# M930C.net
KiCad netlist of a schematic drawn in EAGLE
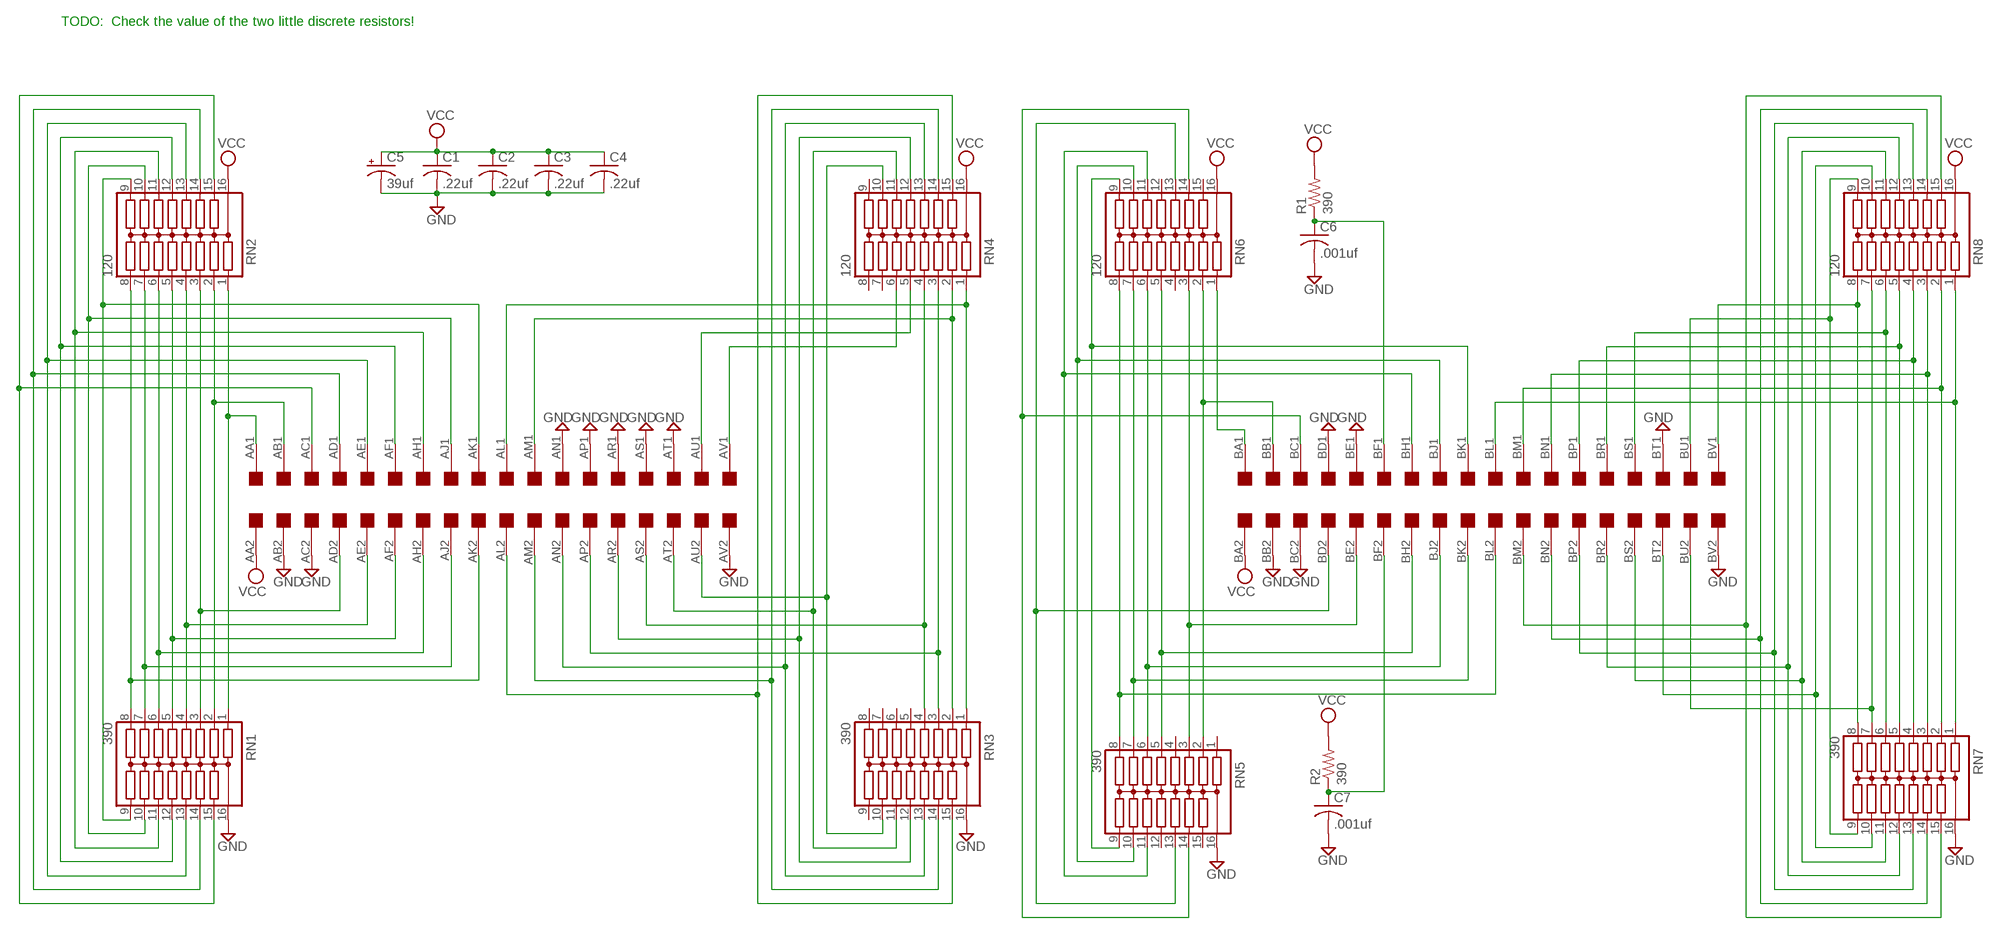
[diagram p0: schematic, sheet 1]

(export (version "E")
  (design (tool "Eeschema 10.0.6"))
  (components
    (comp (ref "C1")
      (value ".22uf")
      (footprint "eagle-import:C050-025X075")
      (libsource (lib "eagle-import") (part "C-US050-025X075"))
    )
    (comp (ref "C2")
      (value ".22uf")
      (footprint "eagle-import:C050-025X075")
      (libsource (lib "eagle-import") (part "C-US050-025X075"))
    )
    (comp (ref "C3")
      (value ".22uf")
      (footprint "eagle-import:C050-025X075")
      (libsource (lib "eagle-import") (part "C-US050-025X075"))
    )
    (comp (ref "C4")
      (value ".22uf")
      (footprint "eagle-import:C050-025X075")
      (libsource (lib "eagle-import") (part "C-US050-025X075"))
    )
    (comp (ref "C5")
      (value "39uf")
      (footprint "eagle-import:E15-5")
      (libsource (lib "eagle-import") (part "CPOL-USE15-5AXIAL"))
    )
    (comp (ref "C6")
      (value ".001uf")
      (footprint "eagle-import:C050-025X075")
      (libsource (lib "eagle-import") (part "C-US050-025X075"))
    )
    (comp (ref "C7")
      (value ".001uf")
      (footprint "eagle-import:C050-025X075")
      (libsource (lib "eagle-import") (part "C-US050-025X075"))
    )
    (comp (ref "R1")
      (value "390")
      (footprint "eagle-import:0207_10")
      (libsource (lib "eagle-import") (part "R-US_0207/10"))
    )
    (comp (ref "R2")
      (value "390")
      (footprint "eagle-import:0207_10")
      (libsource (lib "eagle-import") (part "R-US_0207/10"))
    )
    (comp (ref "RN1")
      (value "390")
      (footprint "eagle-import:DIL16")
      (libsource (lib "eagle-import") (part "15R"))
    )
    (comp (ref "RN2")
      (value "120")
      (footprint "eagle-import:DIL16")
      (libsource (lib "eagle-import") (part "15R"))
    )
    (comp (ref "RN3")
      (value "390")
      (footprint "eagle-import:DIL16")
      (libsource (lib "eagle-import") (part "15R"))
    )
    (comp (ref "RN4")
      (value "120")
      (footprint "eagle-import:DIL16")
      (libsource (lib "eagle-import") (part "15R"))
    )
    (comp (ref "RN5")
      (value "390")
      (footprint "eagle-import:DIL16")
      (libsource (lib "eagle-import") (part "15R"))
    )
    (comp (ref "RN6")
      (value "120")
      (footprint "eagle-import:DIL16")
      (libsource (lib "eagle-import") (part "15R"))
    )
    (comp (ref "RN7")
      (value "390")
      (footprint "eagle-import:DIL16")
      (libsource (lib "eagle-import") (part "15R"))
    )
    (comp (ref "RN8")
      (value "120")
      (footprint "eagle-import:DIL16")
      (libsource (lib "eagle-import") (part "15R"))
    )
    (comp (ref "U$1")
      (value "DOUBLE")
      (footprint "eagle-import:EDGE-CON4")
      (libsource (lib "eagle-import") (part "DOUBLE"))
    )
  )
  (nets
    (net (code "1") (name "GND") (class "Default")
      (node (ref "C1") (pin "2") (pinfunction "2_2") (pintype "passive"))
      (node (ref "C2") (pin "2") (pinfunction "2_2") (pintype "passive"))
      (node (ref "C3") (pin "2") (pinfunction "2_2") (pintype "passive"))
      (node (ref "C4") (pin "2") (pinfunction "2_2") (pintype "passive"))
      (node (ref "C5") (pin "-") (pinfunction "-_-") (pintype "passive"))
      (node (ref "C6") (pin "2") (pinfunction "2_2") (pintype "passive"))
      (node (ref "C7") (pin "2") (pinfunction "2_2") (pintype "passive"))
      (node (ref "RN1") (pin "16") (pinfunction "16_16") (pintype "passive"))
      (node (ref "RN3") (pin "16") (pinfunction "16_16") (pintype "passive"))
      (node (ref "RN5") (pin "16") (pinfunction "16_16") (pintype "passive"))
      (node (ref "RN7") (pin "16") (pinfunction "16_16") (pintype "passive"))
      (node (ref "U$1") (pin "AB2") (pinfunction "1_AB2") (pintype "bidirectional"))
      (node (ref "U$1") (pin "AC2") (pinfunction "1_AC2") (pintype "bidirectional"))
      (node (ref "U$1") (pin "AN1") (pinfunction "1_AN1") (pintype "bidirectional"))
      (node (ref "U$1") (pin "AP1") (pinfunction "1_AP1") (pintype "bidirectional"))
      (node (ref "U$1") (pin "AR1") (pinfunction "1_AR1") (pintype "bidirectional"))
      (node (ref "U$1") (pin "AS1") (pinfunction "1_AS1") (pintype "bidirectional"))
      (node (ref "U$1") (pin "AT1") (pinfunction "1_AT1") (pintype "bidirectional"))
      (node (ref "U$1") (pin "AV2") (pinfunction "1_AV2") (pintype "bidirectional"))
      (node (ref "U$1") (pin "BB2") (pinfunction "1_BB2") (pintype "bidirectional"))
      (node (ref "U$1") (pin "BC2") (pinfunction "1_BC2") (pintype "bidirectional"))
      (node (ref "U$1") (pin "BD1") (pinfunction "1_BD1") (pintype "bidirectional"))
      (node (ref "U$1") (pin "BE1") (pinfunction "1_BE1") (pintype "bidirectional"))
      (node (ref "U$1") (pin "BT1") (pinfunction "1_BT1") (pintype "bidirectional"))
      (node (ref "U$1") (pin "BV2") (pinfunction "1_BV2") (pintype "bidirectional"))
    )
    (net (code "2") (name "Net-(U$1A-1)") (class "Default")
      (node (ref "RN1") (pin "1") (pinfunction "1_1") (pintype "passive"))
      (node (ref "RN2") (pin "1") (pinfunction "1_1") (pintype "passive"))
      (node (ref "U$1") (pin "AA1") (pinfunction "1_AA1") (pintype "bidirectional"))
    )
    (net (code "3") (name "Net-(U$1AB-1)") (class "Default")
      (node (ref "RN3") (pin "12") (pinfunction "12_12") (pintype "passive"))
      (node (ref "RN4") (pin "12") (pinfunction "12_12") (pintype "passive"))
      (node (ref "U$1") (pin "AR2") (pinfunction "1_AR2") (pintype "bidirectional"))
    )
    (net (code "4") (name "Net-(U$1AD-1)") (class "Default")
      (node (ref "RN3") (pin "4") (pinfunction "4_4") (pintype "passive"))
      (node (ref "RN4") (pin "4") (pinfunction "4_4") (pintype "passive"))
      (node (ref "U$1") (pin "AS2") (pinfunction "1_AS2") (pintype "bidirectional"))
    )
    (net (code "5") (name "Net-(U$1AF-1)") (class "Default")
      (node (ref "RN3") (pin "11") (pinfunction "11_11") (pintype "passive"))
      (node (ref "RN4") (pin "11") (pinfunction "11_11") (pintype "passive"))
      (node (ref "U$1") (pin "AT2") (pinfunction "1_AT2") (pintype "bidirectional"))
    )
    (net (code "6") (name "Net-(U$1AG-1)") (class "Default")
      (node (ref "RN4") (pin "5") (pinfunction "5_5") (pintype "passive"))
      (node (ref "U$1") (pin "AU1") (pinfunction "1_AU1") (pintype "bidirectional"))
    )
    (net (code "7") (name "Net-(U$1AH-1)") (class "Default")
      (node (ref "RN3") (pin "10") (pinfunction "10_10") (pintype "passive"))
      (node (ref "RN4") (pin "10") (pinfunction "10_10") (pintype "passive"))
      (node (ref "U$1") (pin "AU2") (pinfunction "1_AU2") (pintype "bidirectional"))
    )
    (net (code "8") (name "Net-(U$1AI-1)") (class "Default")
      (node (ref "RN4") (pin "6") (pinfunction "6_6") (pintype "passive"))
      (node (ref "U$1") (pin "AV1") (pinfunction "1_AV1") (pintype "bidirectional"))
    )
    (net (code "9") (name "Net-(U$1AK-1)") (class "Default")
      (node (ref "RN6") (pin "1") (pinfunction "1_1") (pintype "passive"))
      (node (ref "U$1") (pin "BA1") (pinfunction "1_BA1") (pintype "bidirectional"))
    )
    (net (code "10") (name "Net-(U$1AM-1)") (class "Default")
      (node (ref "RN5") (pin "2") (pinfunction "2_2") (pintype "passive"))
      (node (ref "RN6") (pin "2") (pinfunction "2_2") (pintype "passive"))
      (node (ref "U$1") (pin "BB1") (pinfunction "1_BB1") (pintype "bidirectional"))
    )
    (net (code "11") (name "Net-(U$1AO-1)") (class "Default")
      (node (ref "RN5") (pin "14") (pinfunction "14_14") (pintype "passive"))
      (node (ref "RN6") (pin "14") (pinfunction "14_14") (pintype "passive"))
      (node (ref "U$1") (pin "BC1") (pinfunction "1_BC1") (pintype "bidirectional"))
    )
    (net (code "12") (name "Net-(U$1AR-1)") (class "Default")
      (node (ref "RN5") (pin "13") (pinfunction "13_13") (pintype "passive"))
      (node (ref "RN6") (pin "13") (pinfunction "13_13") (pintype "passive"))
      (node (ref "U$1") (pin "BD2") (pinfunction "1_BD2") (pintype "bidirectional"))
    )
    (net (code "13") (name "Net-(U$1AT-1)") (class "Default")
      (node (ref "RN5") (pin "3") (pinfunction "3_3") (pintype "passive"))
      (node (ref "RN6") (pin "3") (pinfunction "3_3") (pintype "passive"))
      (node (ref "U$1") (pin "BE2") (pinfunction "1_BE2") (pintype "bidirectional"))
    )
    (net (code "14") (name "Net-(U$1AU-1)") (class "Default")
      (node (ref "C6") (pin "1") (pinfunction "1_1") (pintype "passive"))
      (node (ref "R1") (pin "1") (pinfunction "1_1") (pintype "passive"))
      (node (ref "U$1") (pin "BF1") (pinfunction "1_BF1") (pintype "bidirectional"))
    )
    (net (code "15") (name "Net-(U$1AV-1)") (class "Default")
      (node (ref "C7") (pin "1") (pinfunction "1_1") (pintype "passive"))
      (node (ref "R2") (pin "1") (pinfunction "1_1") (pintype "passive"))
      (node (ref "U$1") (pin "BF2") (pinfunction "1_BF2") (pintype "bidirectional"))
    )
    (net (code "16") (name "Net-(U$1AW-1)") (class "Default")
      (node (ref "RN5") (pin "11") (pinfunction "11_11") (pintype "passive"))
      (node (ref "RN6") (pin "11") (pinfunction "11_11") (pintype "passive"))
      (node (ref "U$1") (pin "BH1") (pinfunction "1_BH1") (pintype "bidirectional"))
    )
    (net (code "17") (name "Net-(U$1AX-1)") (class "Default")
      (node (ref "RN5") (pin "5") (pinfunction "5_5") (pintype "passive"))
      (node (ref "RN6") (pin "5") (pinfunction "5_5") (pintype "passive"))
      (node (ref "U$1") (pin "BH2") (pinfunction "1_BH2") (pintype "bidirectional"))
    )
    (net (code "18") (name "Net-(U$1AY-1)") (class "Default")
      (node (ref "RN5") (pin "10") (pinfunction "10_10") (pintype "passive"))
      (node (ref "RN6") (pin "10") (pinfunction "10_10") (pintype "passive"))
      (node (ref "U$1") (pin "BJ1") (pinfunction "1_BJ1") (pintype "bidirectional"))
    )
    (net (code "19") (name "Net-(U$1AZ-1)") (class "Default")
      (node (ref "RN5") (pin "6") (pinfunction "6_6") (pintype "passive"))
      (node (ref "RN6") (pin "6") (pinfunction "6_6") (pintype "passive"))
      (node (ref "U$1") (pin "BJ2") (pinfunction "1_BJ2") (pintype "bidirectional"))
    )
    (net (code "20") (name "Net-(U$1BA-1)") (class "Default")
      (node (ref "RN5") (pin "9") (pinfunction "9_9") (pintype "passive"))
      (node (ref "RN6") (pin "9") (pinfunction "9_9") (pintype "passive"))
      (node (ref "U$1") (pin "BK1") (pinfunction "1_BK1") (pintype "bidirectional"))
    )
    (net (code "21") (name "Net-(U$1BB-1)") (class "Default")
      (node (ref "RN5") (pin "7") (pinfunction "7_7") (pintype "passive"))
      (node (ref "RN6") (pin "7") (pinfunction "7_7") (pintype "passive"))
      (node (ref "U$1") (pin "BK2") (pinfunction "1_BK2") (pintype "bidirectional"))
    )
    (net (code "22") (name "Net-(U$1BC-1)") (class "Default")
      (node (ref "RN7") (pin "1") (pinfunction "1_1") (pintype "passive"))
      (node (ref "RN8") (pin "1") (pinfunction "1_1") (pintype "passive"))
      (node (ref "U$1") (pin "BL1") (pinfunction "1_BL1") (pintype "bidirectional"))
    )
    (net (code "23") (name "Net-(U$1BD-1)") (class "Default")
      (node (ref "RN5") (pin "8") (pinfunction "8_8") (pintype "passive"))
      (node (ref "RN6") (pin "8") (pinfunction "8_8") (pintype "passive"))
      (node (ref "U$1") (pin "BL2") (pinfunction "1_BL2") (pintype "bidirectional"))
    )
    (net (code "24") (name "Net-(U$1BE-1)") (class "Default")
      (node (ref "RN7") (pin "2") (pinfunction "2_2") (pintype "passive"))
      (node (ref "RN8") (pin "2") (pinfunction "2_2") (pintype "passive"))
      (node (ref "U$1") (pin "BM1") (pinfunction "1_BM1") (pintype "bidirectional"))
    )
    (net (code "25") (name "Net-(U$1BF-1)") (class "Default")
      (node (ref "RN7") (pin "15") (pinfunction "15_15") (pintype "passive"))
      (node (ref "RN8") (pin "15") (pinfunction "15_15") (pintype "passive"))
      (node (ref "U$1") (pin "BM2") (pinfunction "1_BM2") (pintype "bidirectional"))
    )
    (net (code "26") (name "Net-(U$1BG-1)") (class "Default")
      (node (ref "RN7") (pin "3") (pinfunction "3_3") (pintype "passive"))
      (node (ref "RN8") (pin "3") (pinfunction "3_3") (pintype "passive"))
      (node (ref "U$1") (pin "BN1") (pinfunction "1_BN1") (pintype "bidirectional"))
    )
    (net (code "27") (name "Net-(U$1BH-1)") (class "Default")
      (node (ref "RN7") (pin "14") (pinfunction "14_14") (pintype "passive"))
      (node (ref "RN8") (pin "14") (pinfunction "14_14") (pintype "passive"))
      (node (ref "U$1") (pin "BN2") (pinfunction "1_BN2") (pintype "bidirectional"))
    )
    (net (code "28") (name "Net-(U$1BI-1)") (class "Default")
      (node (ref "RN7") (pin "4") (pinfunction "4_4") (pintype "passive"))
      (node (ref "RN8") (pin "4") (pinfunction "4_4") (pintype "passive"))
      (node (ref "U$1") (pin "BP1") (pinfunction "1_BP1") (pintype "bidirectional"))
    )
    (net (code "29") (name "Net-(U$1BJ-1)") (class "Default")
      (node (ref "RN7") (pin "13") (pinfunction "13_13") (pintype "passive"))
      (node (ref "RN8") (pin "13") (pinfunction "13_13") (pintype "passive"))
      (node (ref "U$1") (pin "BP2") (pinfunction "1_BP2") (pintype "bidirectional"))
    )
    (net (code "30") (name "Net-(U$1BK-1)") (class "Default")
      (node (ref "RN7") (pin "5") (pinfunction "5_5") (pintype "passive"))
      (node (ref "RN8") (pin "5") (pinfunction "5_5") (pintype "passive"))
      (node (ref "U$1") (pin "BR1") (pinfunction "1_BR1") (pintype "bidirectional"))
    )
    (net (code "31") (name "Net-(U$1BL-1)") (class "Default")
      (node (ref "RN7") (pin "12") (pinfunction "12_12") (pintype "passive"))
      (node (ref "RN8") (pin "12") (pinfunction "12_12") (pintype "passive"))
      (node (ref "U$1") (pin "BR2") (pinfunction "1_BR2") (pintype "bidirectional"))
    )
    (net (code "32") (name "Net-(U$1BM-1)") (class "Default")
      (node (ref "RN7") (pin "6") (pinfunction "6_6") (pintype "passive"))
      (node (ref "RN8") (pin "6") (pinfunction "6_6") (pintype "passive"))
      (node (ref "U$1") (pin "BS1") (pinfunction "1_BS1") (pintype "bidirectional"))
    )
    (net (code "33") (name "Net-(U$1BN-1)") (class "Default")
      (node (ref "RN7") (pin "11") (pinfunction "11_11") (pintype "passive"))
      (node (ref "RN8") (pin "11") (pinfunction "11_11") (pintype "passive"))
      (node (ref "U$1") (pin "BS2") (pinfunction "1_BS2") (pintype "bidirectional"))
    )
    (net (code "34") (name "Net-(U$1BP-1)") (class "Default")
      (node (ref "RN7") (pin "10") (pinfunction "10_10") (pintype "passive"))
      (node (ref "RN8") (pin "10") (pinfunction "10_10") (pintype "passive"))
      (node (ref "U$1") (pin "BT2") (pinfunction "1_BT2") (pintype "bidirectional"))
    )
    (net (code "35") (name "Net-(U$1BQ-1)") (class "Default")
      (node (ref "RN7") (pin "9") (pinfunction "9_9") (pintype "passive"))
      (node (ref "RN8") (pin "9") (pinfunction "9_9") (pintype "passive"))
      (node (ref "U$1") (pin "BU1") (pinfunction "1_BU1") (pintype "bidirectional"))
    )
    (net (code "36") (name "Net-(U$1BR-1)") (class "Default")
      (node (ref "RN7") (pin "7") (pinfunction "7_7") (pintype "passive"))
      (node (ref "RN8") (pin "7") (pinfunction "7_7") (pintype "passive"))
      (node (ref "U$1") (pin "BU2") (pinfunction "1_BU2") (pintype "bidirectional"))
    )
    (net (code "37") (name "Net-(U$1BS-1)") (class "Default")
      (node (ref "RN7") (pin "8") (pinfunction "8_8") (pintype "passive"))
      (node (ref "RN8") (pin "8") (pinfunction "8_8") (pintype "passive"))
      (node (ref "U$1") (pin "BV1") (pinfunction "1_BV1") (pintype "bidirectional"))
    )
    (net (code "38") (name "Net-(U$1C-1)") (class "Default")
      (node (ref "RN1") (pin "2") (pinfunction "2_2") (pintype "passive"))
      (node (ref "RN2") (pin "2") (pinfunction "2_2") (pintype "passive"))
      (node (ref "U$1") (pin "AB1") (pinfunction "1_AB1") (pintype "bidirectional"))
    )
    (net (code "39") (name "Net-(U$1E-1)") (class "Default")
      (node (ref "RN1") (pin "15") (pinfunction "15_15") (pintype "passive"))
      (node (ref "RN2") (pin "15") (pinfunction "15_15") (pintype "passive"))
      (node (ref "U$1") (pin "AC1") (pinfunction "1_AC1") (pintype "bidirectional"))
    )
    (net (code "40") (name "Net-(U$1G-1)") (class "Default")
      (node (ref "RN1") (pin "14") (pinfunction "14_14") (pintype "passive"))
      (node (ref "RN2") (pin "14") (pinfunction "14_14") (pintype "passive"))
      (node (ref "U$1") (pin "AD1") (pinfunction "1_AD1") (pintype "bidirectional"))
    )
    (net (code "41") (name "Net-(U$1H-1)") (class "Default")
      (node (ref "RN1") (pin "3") (pinfunction "3_3") (pintype "passive"))
      (node (ref "RN2") (pin "3") (pinfunction "3_3") (pintype "passive"))
      (node (ref "U$1") (pin "AD2") (pinfunction "1_AD2") (pintype "bidirectional"))
    )
    (net (code "42") (name "Net-(U$1I-1)") (class "Default")
      (node (ref "RN1") (pin "13") (pinfunction "13_13") (pintype "passive"))
      (node (ref "RN2") (pin "13") (pinfunction "13_13") (pintype "passive"))
      (node (ref "U$1") (pin "AE1") (pinfunction "1_AE1") (pintype "bidirectional"))
    )
    (net (code "43") (name "Net-(U$1J-1)") (class "Default")
      (node (ref "RN1") (pin "4") (pinfunction "4_4") (pintype "passive"))
      (node (ref "RN2") (pin "4") (pinfunction "4_4") (pintype "passive"))
      (node (ref "U$1") (pin "AE2") (pinfunction "1_AE2") (pintype "bidirectional"))
    )
    (net (code "44") (name "Net-(U$1K-1)") (class "Default")
      (node (ref "RN1") (pin "12") (pinfunction "12_12") (pintype "passive"))
      (node (ref "RN2") (pin "12") (pinfunction "12_12") (pintype "passive"))
      (node (ref "U$1") (pin "AF1") (pinfunction "1_AF1") (pintype "bidirectional"))
    )
    (net (code "45") (name "Net-(U$1L-1)") (class "Default")
      (node (ref "RN1") (pin "5") (pinfunction "5_5") (pintype "passive"))
      (node (ref "RN2") (pin "5") (pinfunction "5_5") (pintype "passive"))
      (node (ref "U$1") (pin "AF2") (pinfunction "1_AF2") (pintype "bidirectional"))
    )
    (net (code "46") (name "Net-(U$1M-1)") (class "Default")
      (node (ref "RN1") (pin "11") (pinfunction "11_11") (pintype "passive"))
      (node (ref "RN2") (pin "11") (pinfunction "11_11") (pintype "passive"))
      (node (ref "U$1") (pin "AH1") (pinfunction "1_AH1") (pintype "bidirectional"))
    )
    (net (code "47") (name "Net-(U$1N-1)") (class "Default")
      (node (ref "RN1") (pin "6") (pinfunction "6_6") (pintype "passive"))
      (node (ref "RN2") (pin "6") (pinfunction "6_6") (pintype "passive"))
      (node (ref "U$1") (pin "AH2") (pinfunction "1_AH2") (pintype "bidirectional"))
    )
    (net (code "48") (name "Net-(U$1O-1)") (class "Default")
      (node (ref "RN1") (pin "10") (pinfunction "10_10") (pintype "passive"))
      (node (ref "RN2") (pin "10") (pinfunction "10_10") (pintype "passive"))
      (node (ref "U$1") (pin "AJ1") (pinfunction "1_AJ1") (pintype "bidirectional"))
    )
    (net (code "49") (name "Net-(U$1P-1)") (class "Default")
      (node (ref "RN1") (pin "7") (pinfunction "7_7") (pintype "passive"))
      (node (ref "RN2") (pin "7") (pinfunction "7_7") (pintype "passive"))
      (node (ref "U$1") (pin "AJ2") (pinfunction "1_AJ2") (pintype "bidirectional"))
    )
    (net (code "50") (name "Net-(U$1Q-1)") (class "Default")
      (node (ref "RN1") (pin "9") (pinfunction "9_9") (pintype "passive"))
      (node (ref "RN2") (pin "9") (pinfunction "9_9") (pintype "passive"))
      (node (ref "U$1") (pin "AK1") (pinfunction "1_AK1") (pintype "bidirectional"))
    )
    (net (code "51") (name "Net-(U$1R-1)") (class "Default")
      (node (ref "RN1") (pin "8") (pinfunction "8_8") (pintype "passive"))
      (node (ref "RN2") (pin "8") (pinfunction "8_8") (pintype "passive"))
      (node (ref "U$1") (pin "AK2") (pinfunction "1_AK2") (pintype "bidirectional"))
    )
    (net (code "52") (name "Net-(U$1S-1)") (class "Default")
      (node (ref "RN3") (pin "1") (pinfunction "1_1") (pintype "passive"))
      (node (ref "RN4") (pin "1") (pinfunction "1_1") (pintype "passive"))
      (node (ref "U$1") (pin "AL1") (pinfunction "1_AL1") (pintype "bidirectional"))
    )
    (net (code "53") (name "Net-(U$1T-1)") (class "Default")
      (node (ref "RN3") (pin "15") (pinfunction "15_15") (pintype "passive"))
      (node (ref "RN4") (pin "15") (pinfunction "15_15") (pintype "passive"))
      (node (ref "U$1") (pin "AL2") (pinfunction "1_AL2") (pintype "bidirectional"))
    )
    (net (code "54") (name "Net-(U$1U-1)") (class "Default")
      (node (ref "RN3") (pin "2") (pinfunction "2_2") (pintype "passive"))
      (node (ref "RN4") (pin "2") (pinfunction "2_2") (pintype "passive"))
      (node (ref "U$1") (pin "AM1") (pinfunction "1_AM1") (pintype "bidirectional"))
    )
    (net (code "55") (name "Net-(U$1V-1)") (class "Default")
      (node (ref "RN3") (pin "14") (pinfunction "14_14") (pintype "passive"))
      (node (ref "RN4") (pin "14") (pinfunction "14_14") (pintype "passive"))
      (node (ref "U$1") (pin "AM2") (pinfunction "1_AM2") (pintype "bidirectional"))
    )
    (net (code "56") (name "Net-(U$1X-1)") (class "Default")
      (node (ref "RN3") (pin "13") (pinfunction "13_13") (pintype "passive"))
      (node (ref "RN4") (pin "13") (pinfunction "13_13") (pintype "passive"))
      (node (ref "U$1") (pin "AN2") (pinfunction "1_AN2") (pintype "bidirectional"))
    )
    (net (code "57") (name "Net-(U$1Z-1)") (class "Default")
      (node (ref "RN3") (pin "3") (pinfunction "3_3") (pintype "passive"))
      (node (ref "RN4") (pin "3") (pinfunction "3_3") (pintype "passive"))
      (node (ref "U$1") (pin "AP2") (pinfunction "1_AP2") (pintype "bidirectional"))
    )
    (net (code "58") (name "VCC") (class "Default")
      (node (ref "C1") (pin "1") (pinfunction "1_1") (pintype "passive"))
      (node (ref "C2") (pin "1") (pinfunction "1_1") (pintype "passive"))
      (node (ref "C3") (pin "1") (pinfunction "1_1") (pintype "passive"))
      (node (ref "C4") (pin "1") (pinfunction "1_1") (pintype "passive"))
      (node (ref "C5") (pin "+") (pinfunction "+_+") (pintype "passive"))
      (node (ref "R1") (pin "2") (pinfunction "2_2") (pintype "passive"))
      (node (ref "R2") (pin "2") (pinfunction "2_2") (pintype "passive"))
      (node (ref "RN2") (pin "16") (pinfunction "16_16") (pintype "passive"))
      (node (ref "RN4") (pin "16") (pinfunction "16_16") (pintype "passive"))
      (node (ref "RN6") (pin "16") (pinfunction "16_16") (pintype "passive"))
      (node (ref "RN8") (pin "16") (pinfunction "16_16") (pintype "passive"))
      (node (ref "U$1") (pin "AA2") (pinfunction "1_AA2") (pintype "bidirectional"))
      (node (ref "U$1") (pin "BA2") (pinfunction "1_BA2") (pintype "bidirectional"))
    )
    (net (code "59") (name "unconnected-(RN3-Pad5)") (class "Default")
      (node (ref "RN3") (pin "5") (pinfunction "5_5") (pintype "passive"))
    )
    (net (code "60") (name "unconnected-(RN3-Pad6)") (class "Default")
      (node (ref "RN3") (pin "6") (pinfunction "6_6") (pintype "passive"))
    )
    (net (code "61") (name "unconnected-(RN3-Pad7)") (class "Default")
      (node (ref "RN3") (pin "7") (pinfunction "7_7") (pintype "passive"))
    )
    (net (code "62") (name "unconnected-(RN3-Pad8)") (class "Default")
      (node (ref "RN3") (pin "8") (pinfunction "8_8") (pintype "passive"))
    )
    (net (code "63") (name "unconnected-(RN3-Pad9)") (class "Default")
      (node (ref "RN3") (pin "9") (pinfunction "9_9") (pintype "passive"))
    )
    (net (code "64") (name "unconnected-(RN4-Pad7)") (class "Default")
      (node (ref "RN4") (pin "7") (pinfunction "7_7") (pintype "passive"))
    )
    (net (code "65") (name "unconnected-(RN4-Pad8)") (class "Default")
      (node (ref "RN4") (pin "8") (pinfunction "8_8") (pintype "passive"))
    )
    (net (code "66") (name "unconnected-(RN4-Pad9)") (class "Default")
      (node (ref "RN4") (pin "9") (pinfunction "9_9") (pintype "passive"))
    )
    (net (code "67") (name "unconnected-(RN5-Pad1)") (class "Default")
      (node (ref "RN5") (pin "1") (pinfunction "1_1") (pintype "passive"))
    )
    (net (code "68") (name "unconnected-(RN5-Pad4)") (class "Default")
      (node (ref "RN5") (pin "4") (pinfunction "4_4") (pintype "passive"))
    )
    (net (code "69") (name "unconnected-(RN5-Pad12)") (class "Default")
      (node (ref "RN5") (pin "12") (pinfunction "12_12") (pintype "passive"))
    )
    (net (code "70") (name "unconnected-(RN5-Pad15)") (class "Default")
      (node (ref "RN5") (pin "15") (pinfunction "15_15") (pintype "passive"))
    )
    (net (code "71") (name "unconnected-(RN6-Pad4)") (class "Default")
      (node (ref "RN6") (pin "4") (pinfunction "4_4") (pintype "passive"))
    )
    (net (code "72") (name "unconnected-(RN6-Pad12)") (class "Default")
      (node (ref "RN6") (pin "12") (pinfunction "12_12") (pintype "passive"))
    )
    (net (code "73") (name "unconnected-(RN6-Pad15)") (class "Default")
      (node (ref "RN6") (pin "15") (pinfunction "15_15") (pintype "passive"))
    )
  )
)
